# ilham_widyo_nugroho_21507334002.net
KiCad netlist of a schematic drawn in EAGLE
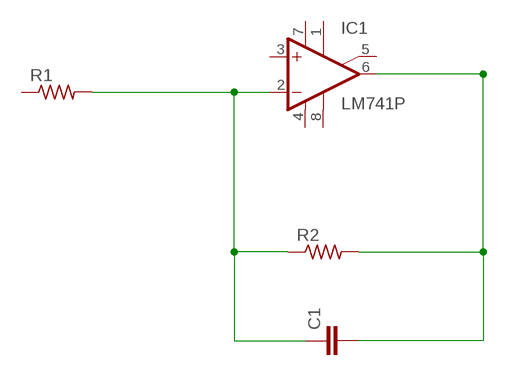
[diagram p0: schematic, sheet 1]

(export (version "E")
  (design (tool "Eeschema 10.0.6"))
  (components
    (comp (ref "C1")
      (value "C2,5-3")
      (footprint "eagle-import:C2.5-3")
      (libsource (lib "eagle-import") (part "C2,5-3"))
    )
    (comp (ref "IC1")
      (value "LM741P")
      (footprint "eagle-import:DIL08")
      (libsource (lib "eagle-import") (part "741PLM"))
    )
    (comp (ref "R1")
      (value "R-US_0204/2V")
      (footprint "eagle-import:0204V")
      (libsource (lib "eagle-import") (part "R-US_0204/2V"))
    )
    (comp (ref "R2")
      (value "R-US_0204/2V")
      (footprint "eagle-import:0204V")
      (libsource (lib "eagle-import") (part "R-US_0204/2V"))
    )
  )
  (nets
    (net (code "1") (name "/V+") (class "Default")
      (node (ref "IC1") (pin "7") (pinfunction "V+_7") (pintype "power_in"))
    )
    (net (code "2") (name "/V-") (class "Default")
      (node (ref "IC1") (pin "4") (pinfunction "V-_4") (pintype "power_in"))
    )
    (net (code "3") (name "Net-(IC1--IN)") (class "Default")
      (node (ref "C1") (pin "1") (pinfunction "1_1") (pintype "passive"))
      (node (ref "IC1") (pin "2") (pinfunction "-IN_2") (pintype "input"))
      (node (ref "R1") (pin "2") (pinfunction "2_2") (pintype "passive"))
      (node (ref "R2") (pin "1") (pinfunction "1_1") (pintype "passive"))
    )
    (net (code "4") (name "Net-(IC1-OUT)") (class "Default")
      (node (ref "C1") (pin "2") (pinfunction "2_2") (pintype "passive"))
      (node (ref "IC1") (pin "6") (pinfunction "OUT_6") (pintype "output"))
      (node (ref "R2") (pin "2") (pinfunction "2_2") (pintype "passive"))
    )
    (net (code "5") (name "unconnected-(IC1-+IN-Pad3)") (class "Default")
      (node (ref "IC1") (pin "3") (pinfunction "+IN_3") (pintype "input"))
    )
    (net (code "6") (name "unconnected-(IC1-ON1-Pad1)") (class "Default")
      (node (ref "IC1") (pin "1") (pinfunction "ON1_1") (pintype "passive"))
    )
    (net (code "7") (name "unconnected-(IC1-ON2-Pad5)") (class "Default")
      (node (ref "IC1") (pin "5") (pinfunction "ON2_5") (pintype "passive"))
    )
    (net (code "8") (name "unconnected-(IC1-OPT-Pad8)") (class "Default")
      (node (ref "IC1") (pin "8") (pinfunction "OPT_8") (pintype "passive"))
    )
    (net (code "9") (name "unconnected-(R1-Pad1)") (class "Default")
      (node (ref "R1") (pin "1") (pinfunction "1_1") (pintype "passive"))
    )
  )
)
